# MIPI_DSI_CSI.net
KiCad netlist of a schematic drawn in Altium Designer
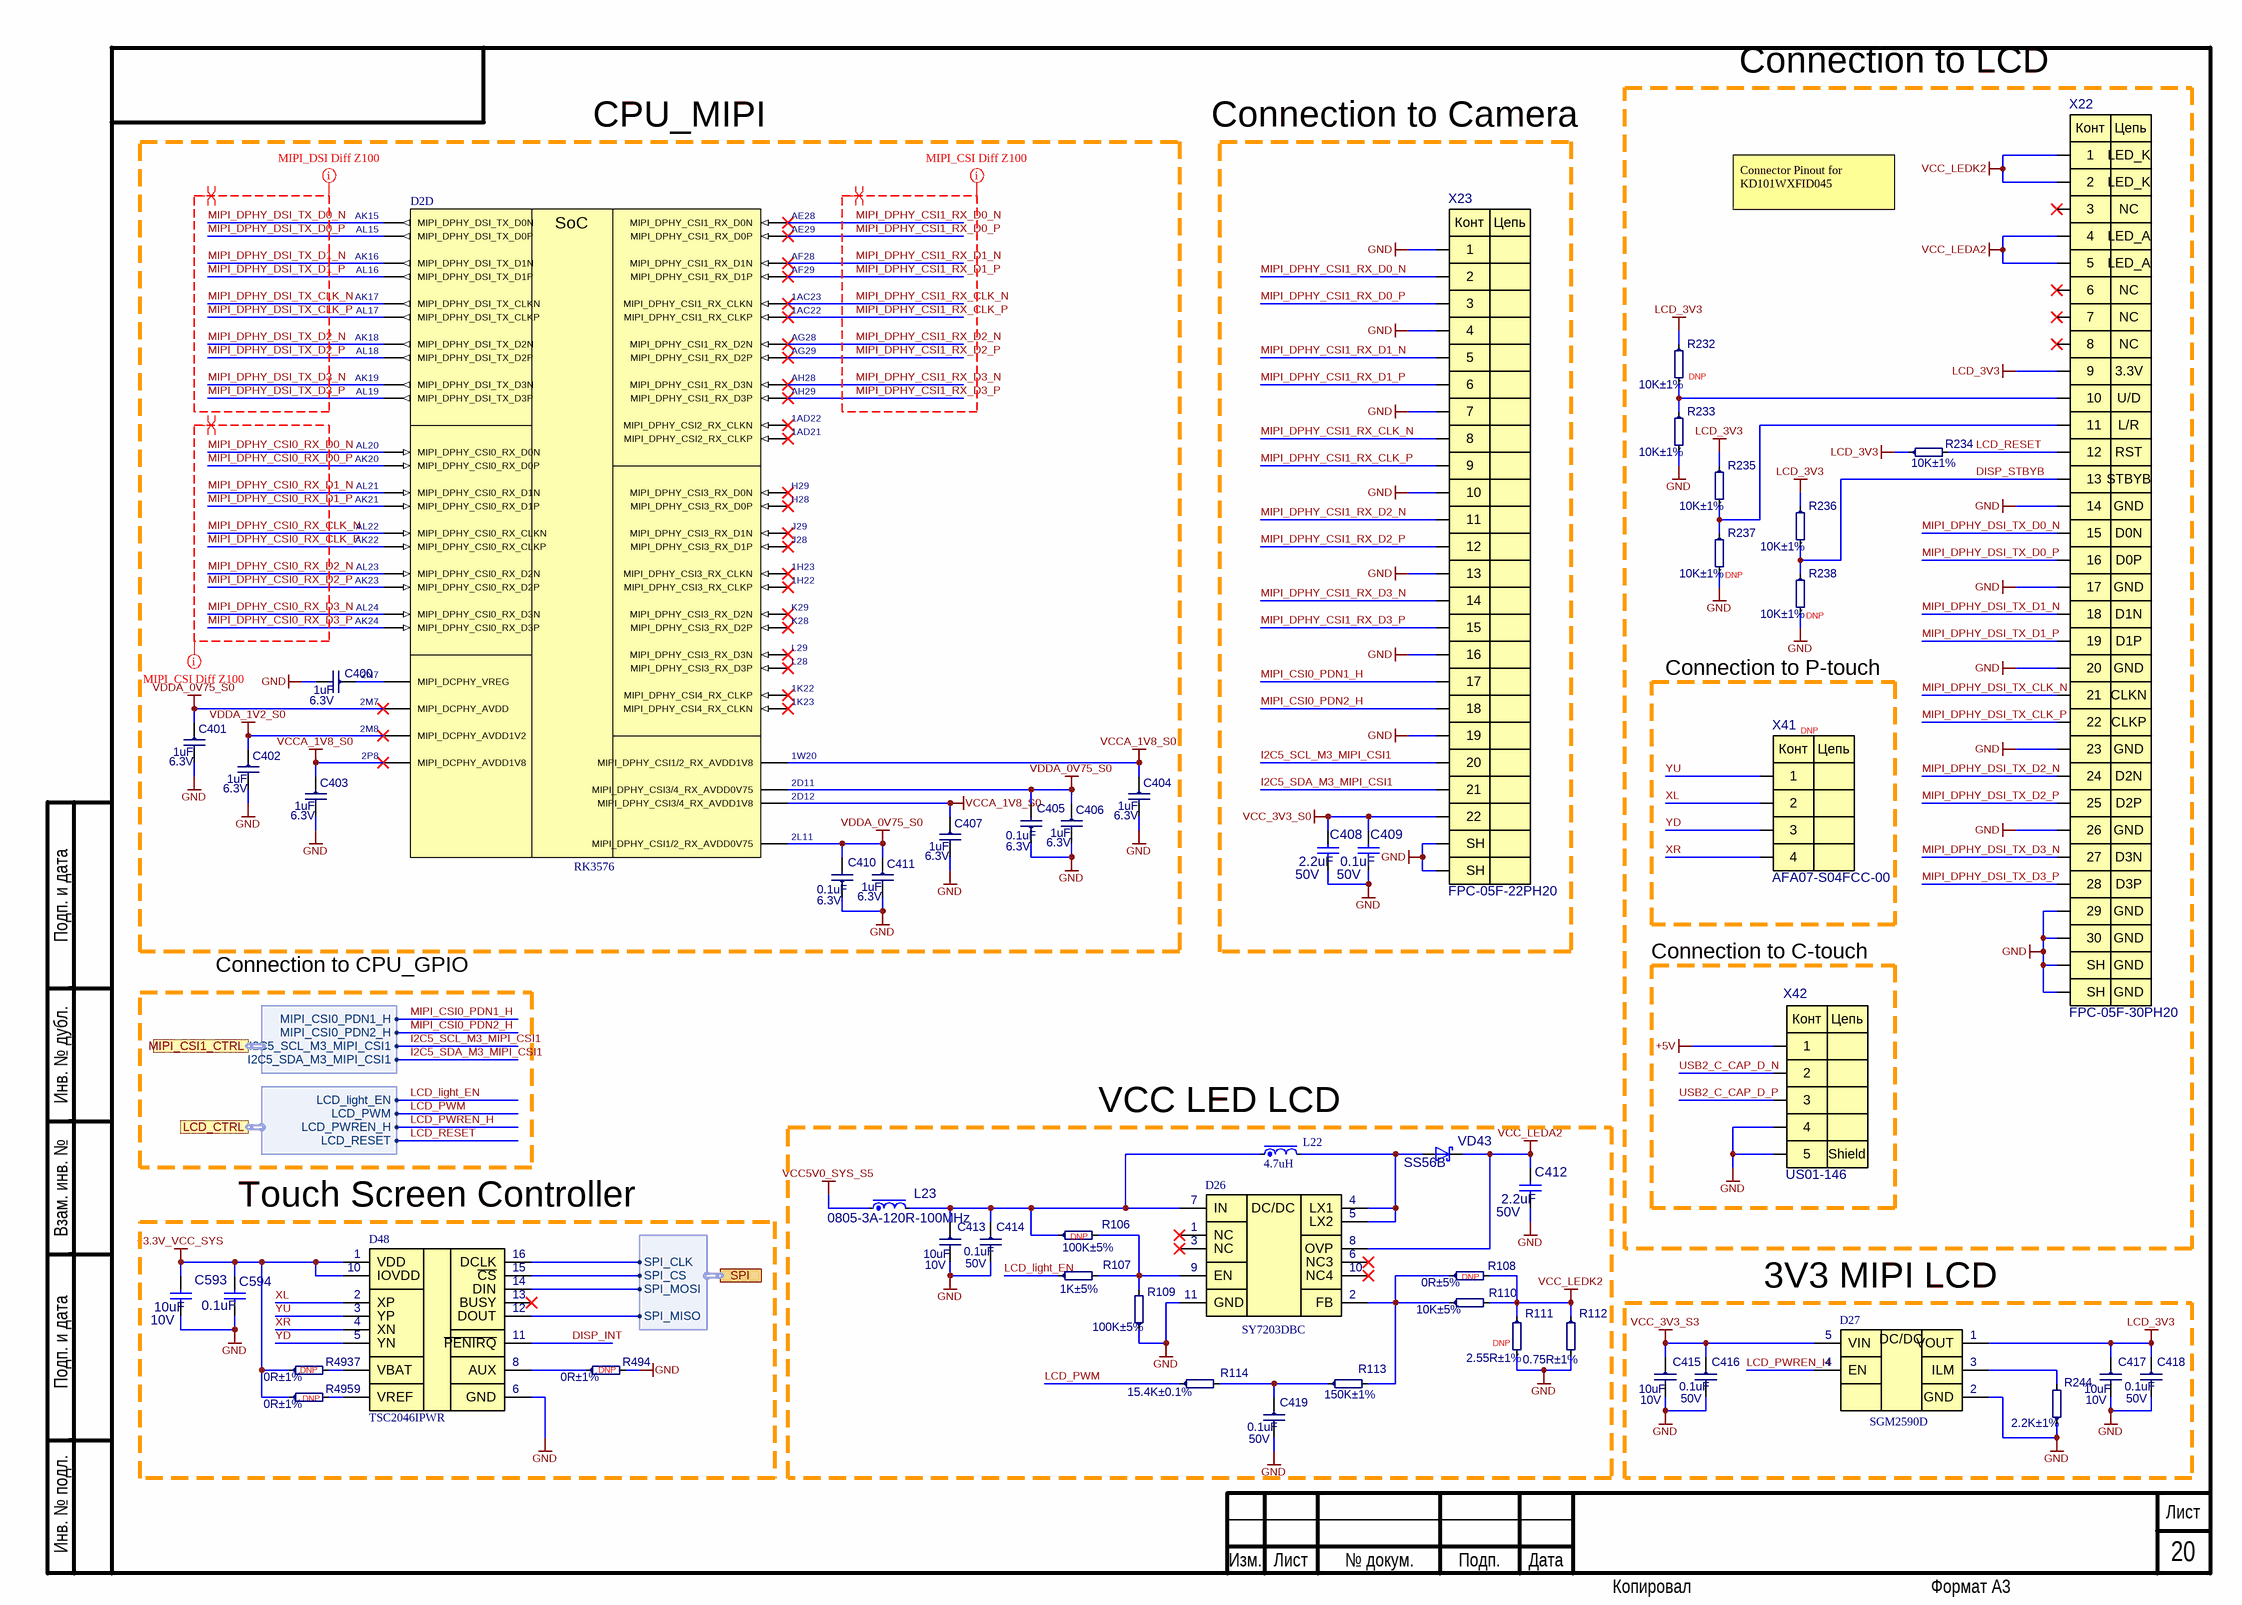
[diagram p0: MIPI_DSI_CSI.SchDoc]

(export (version "E")
  (design (tool "Eeschema 10.0.6"))
  (components
    (comp (ref "C400")
      (value "1uF")
      (footprint "C0201")
      (fields
        (field (name "VOLTAGE") "6.3V")
        (field (name "PART NUMBER") "0201-X5R-6.3V-1uF±20%")
        (field (name "TOLERANCE") "20%")
        (field (name "MANUFACTURER") "Murata Electronics")
      )
      (libsource (lib "ATB") (part "C"))
    )
    (comp (ref "C401")
      (value "1uF")
      (footprint "C0201")
      (fields
        (field (name "VOLTAGE") "6.3V")
        (field (name "PART NUMBER") "0201-X5R-6.3V-1uF±20%")
        (field (name "TOLERANCE") "20%")
        (field (name "MANUFACTURER") "Murata Electronics")
      )
      (libsource (lib "ATB") (part "C"))
    )
    (comp (ref "C402")
      (value "1uF")
      (footprint "C0201")
      (fields
        (field (name "VOLTAGE") "6.3V")
        (field (name "PART NUMBER") "0201-X5R-6.3V-1uF±20%")
        (field (name "TOLERANCE") "20%")
        (field (name "MANUFACTURER") "Murata Electronics")
      )
      (libsource (lib "ATB") (part "C"))
    )
    (comp (ref "C403")
      (value "1uF")
      (footprint "C0201")
      (fields
        (field (name "VOLTAGE") "6.3V")
        (field (name "PART NUMBER") "0201-X5R-6.3V-1uF±20%")
        (field (name "TOLERANCE") "20%")
        (field (name "MANUFACTURER") "Murata Electronics")
      )
      (libsource (lib "ATB") (part "C"))
    )
    (comp (ref "C404")
      (value "1uF")
      (footprint "C0201")
      (fields
        (field (name "VOLTAGE") "6.3V")
        (field (name "PART NUMBER") "0201-X5R-6.3V-1uF±20%")
        (field (name "TOLERANCE") "20%")
        (field (name "MANUFACTURER") "Murata Electronics")
      )
      (libsource (lib "ATB") (part "C"))
    )
    (comp (ref "C405")
      (value "0.1uF")
      (footprint "C0201")
      (fields
        (field (name "VOLTAGE") "6.3V")
        (field (name "PART NUMBER") "0201-X5R-6.3V-0.1uF±10%")
        (field (name "TOLERANCE") "10%")
        (field (name "MANUFACTURER") "Yageo")
      )
      (libsource (lib "ATB") (part "C"))
    )
    (comp (ref "C406")
      (value "1uF")
      (footprint "C0201")
      (fields
        (field (name "VOLTAGE") "6.3V")
        (field (name "PART NUMBER") "0201-X5R-6.3V-1uF±20%")
        (field (name "TOLERANCE") "20%")
        (field (name "MANUFACTURER") "Murata Electronics")
      )
      (libsource (lib "ATB") (part "C"))
    )
    (comp (ref "C407")
      (value "1uF")
      (footprint "C0201")
      (fields
        (field (name "VOLTAGE") "6.3V")
        (field (name "PART NUMBER") "0201-X5R-6.3V-1uF±20%")
        (field (name "TOLERANCE") "20%")
        (field (name "MANUFACTURER") "Murata Electronics")
      )
      (libsource (lib "ATB") (part "C"))
    )
    (comp (ref "C408")
      (value "2.2uF")
      (footprint "C0805")
      (fields
        (field (name "PART NUMBER") "0805-X7R-50V-2.2uF±10%")
        (field (name "VOLTAGE") "50V")
        (field (name "TOLERANCE") "10%")
        (field (name "MANUFACTURER") "Yageo")
      )
      (libsource (lib "") (part "C_1"))
    )
    (comp (ref "C409")
      (value "0.1uF")
      (footprint "C0402")
      (fields
        (field (name "PART NUMBER") "0402-X5R-50V-0.1uF±10%")
        (field (name "VOLTAGE") "50V")
        (field (name "TOLERANCE") "10%")
        (field (name "MANUFACTURER") "Yageo")
      )
      (libsource (lib "") (part "C_1"))
    )
    (comp (ref "C410")
      (value "0.1uF")
      (footprint "C0201")
      (fields
        (field (name "VOLTAGE") "6.3V")
        (field (name "PART NUMBER") "0201-X5R-6.3V-0.1uF±10%")
        (field (name "TOLERANCE") "10%")
        (field (name "MANUFACTURER") "Yageo")
      )
      (libsource (lib "ATB") (part "C"))
    )
    (comp (ref "C411")
      (value "1uF")
      (footprint "C0201")
      (fields
        (field (name "VOLTAGE") "6.3V")
        (field (name "PART NUMBER") "0201-X5R-6.3V-1uF±20%")
        (field (name "TOLERANCE") "20%")
        (field (name "MANUFACTURER") "Murata Electronics")
      )
      (libsource (lib "ATB") (part "C"))
    )
    (comp (ref "C412")
      (value "2.2uF")
      (footprint "C0805")
      (fields
        (field (name "PART NUMBER") "0805-X7R-50V-2.2uF±10%")
        (field (name "VOLTAGE") "50V")
        (field (name "TOLERANCE") "10%")
        (field (name "MANUFACTURER") "Yageo")
      )
      (libsource (lib "") (part "C_1"))
    )
    (comp (ref "C413")
      (value "10uF")
      (footprint "C0603")
      (fields
        (field (name "VOLTAGE") "10V")
        (field (name "PART NUMBER") "0603-X5R-10V-10uF±10%")
        (field (name "TOLERANCE") "10%")
        (field (name "MANUFACTURER") "Yageo")
      )
      (libsource (lib "ATB") (part "C"))
    )
    (comp (ref "C414")
      (value "0.1uF")
      (footprint "C0402")
      (fields
        (field (name "VOLTAGE") "50V")
        (field (name "PART NUMBER") "0402-X5R-50V-0.1uF±10%")
        (field (name "TOLERANCE") "10%")
        (field (name "MANUFACTURER") "Yageo")
      )
      (libsource (lib "ATB") (part "C"))
    )
    (comp (ref "C415")
      (value "10uF")
      (footprint "C0603")
      (fields
        (field (name "VOLTAGE") "10V")
        (field (name "PART NUMBER") "0603-X5R-10V-10uF±10%")
        (field (name "TOLERANCE") "10%")
        (field (name "MANUFACTURER") "Yageo")
      )
      (libsource (lib "ATB") (part "C"))
    )
    (comp (ref "C416")
      (value "0.1uF")
      (footprint "C0402")
      (fields
        (field (name "VOLTAGE") "50V")
        (field (name "PART NUMBER") "0402-X5R-50V-0.1uF±10%")
        (field (name "TOLERANCE") "10%")
        (field (name "MANUFACTURER") "Yageo")
      )
      (libsource (lib "ATB") (part "C"))
    )
    (comp (ref "C417")
      (value "10uF")
      (footprint "C0603")
      (fields
        (field (name "VOLTAGE") "10V")
        (field (name "PART NUMBER") "0603-X5R-10V-10uF±10%")
        (field (name "TOLERANCE") "10%")
        (field (name "MANUFACTURER") "Yageo")
      )
      (libsource (lib "ATB") (part "C"))
    )
    (comp (ref "C418")
      (value "0.1uF")
      (footprint "C0402")
      (fields
        (field (name "VOLTAGE") "50V")
        (field (name "PART NUMBER") "0402-X5R-50V-0.1uF±10%")
        (field (name "TOLERANCE") "10%")
        (field (name "MANUFACTURER") "Yageo")
      )
      (libsource (lib "ATB") (part "C"))
    )
    (comp (ref "C419")
      (value "0.1uF")
      (footprint "C0402")
      (fields
        (field (name "VOLTAGE") "50V")
        (field (name "PART NUMBER") "0402-X5R-50V-0.1uF±10%")
        (field (name "TOLERANCE") "10%")
        (field (name "MANUFACTURER") "Yageo")
      )
      (libsource (lib "ATB") (part "C"))
    )
    (comp (ref "C593")
      (value "10uF")
      (footprint "C0402")
      (fields
        (field (name "PART NUMBER") "0402-X5R-10V-10uF±20")
        (field (name "VOLTAGE") "10V")
        (field (name "TOLERANCE") "20%")
        (field (name "MANUFACTURER") "Samsung")
      )
      (libsource (lib "") (part "C_1"))
    )
    (comp (ref "C594")
      (value "0.1uF")
      (footprint "C0402")
      (fields
        (field (name "PART NUMBER") "0402-X5R-50V-0.1uF±10%")
        (field (name "VOLTAGE") "50V")
        (field (name "TOLERANCE") "10%")
      )
      (libsource (lib "") (part "C_1"))
    )
    (comp (ref "D2")
      (value "RK3576")
      (footprint "BGAFCCSP698L")
      (description "SoC 4xCortex-A72@2.2Ghz+4xCortex-A53@2Ghz, LPDDR4/4X/5/5X, SDIO/eMMC/UFS/FSPI, BGA 16.1x17.2x1.0mm")
      (fields (field (name "MANUFACTURER") "Rockship"))
      (libsource (lib "ATB") (part "RK3576"))
    )
    (comp (ref "D26")
      (value "SY7203DBC")
      (footprint "SY7203DBC")
      (description "1MHz PWM Boost 1 DC-DC 2.8V~30V DFN-10-EP(3x3) LED Drivers ICs RoHS")
      (fields (field (name "MANUFACTURER") "Silergy"))
      (libsource (lib "LIB_RK") (part "SY7203DBC"))
    )
    (comp (ref "D27")
      (value "SGM2590D")
      (footprint "SGM2590D")
      (fields (field (name "MANUFACTURER") "SGM"))
      (libsource (lib "LIB_RK") (part "SGM2590D"))
    )
    (comp (ref "D48")
      (value "TSC2046IPWR")
      (footprint "TSC2046IPWR")
      (description "SPI 12 2.2V~5.25V TSSOP-16 Touch Screen Controllers")
      (fields (field (name "MANUFACTURER") "Texas"))
      (libsource (lib "LIB_RK") (part "TSC2046IPWR"))
    )
    (comp (ref "L22")
      (value "4.7uH")
      (footprint "SWPA6045S4R7MT")
      (description "SMD Power Inductor")
      (fields (field (name "PART NUMBER") "SWPA6045S4R7MT") (field (name "MANUFACTURER") "Sunlord"))
      (libsource (lib "LIB_RK") (part "SWPA6045S4R7MT"))
    )
    (comp (ref "L23")
      (value "0805-3A-120R-100MHz")
      (footprint "L0805")
      (fields
        (field (name "PART NUMBER") "CBM201209U121T")
        (field (name "TOLERANCE") "25%")
        (field (name "MANUFACTURER") "FH")
      )
      (libsource (lib "ATB") (part "L"))
    )
    (comp (ref "R106")
      (value "100K±5%")
      (footprint "R0402")
      (fields
        (field (name "PART NUMBER") "0402-0.0625W-100K-100ppm±5%")
        (field (name "TOLERANCE") "5%")
        (field (name "MANUFACTURER") "Yageo")
      )
      (libsource (lib "ATB") (part "R"))
    )
    (comp (ref "R107")
      (value "1K±5%")
      (footprint "R0402")
      (fields
        (field (name "PART NUMBER") "0402-0.0625W-1K-100ppm±5%")
        (field (name "TOLERANCE") "5%")
        (field (name "MANUFACTURER") "Yageo")
      )
      (libsource (lib "ATB") (part "R"))
    )
    (comp (ref "R108")
      (value "0R±5%")
      (footprint "R1206")
      (fields
        (field (name "PART NUMBER") "1206-0.25W-0R-200ppm±5%")
        (field (name "TOLERANCE") "5%")
        (field (name "MANUFACTURER") "Yageo")
      )
      (libsource (lib "ATB") (part "R"))
    )
    (comp (ref "R109")
      (value "100K±5%")
      (footprint "R0402")
      (fields
        (field (name "PART NUMBER") "0402-0.0625W-100K-100ppm±5%")
        (field (name "TOLERANCE") "5%")
        (field (name "MANUFACTURER") "Yageo")
      )
      (libsource (lib "ATB") (part "R"))
    )
    (comp (ref "R110")
      (value "10K±5%")
      (footprint "R1206")
      (fields
        (field (name "PART NUMBER") "1206-0.25W-10K-100ppm±5%")
        (field (name "TOLERANCE") "5%")
        (field (name "MANUFACTURER") "Yageo")
      )
      (libsource (lib "ATB") (part "R"))
    )
    (comp (ref "R111")
      (value "2.55R±1%")
      (footprint "R1206")
      (fields
        (field (name "PART NUMBER") "1206-0.25W-2.55R-100ppm±1%")
        (field (name "TOLERANCE") "1%")
        (field (name "MANUFACTURER") "Yageo")
      )
      (libsource (lib "ATB") (part "R"))
    )
    (comp (ref "R112")
      (value "0.75R±1%")
      (footprint "R1206")
      (fields
        (field (name "PART NUMBER") "1206-0.25W-0.75R-100ppm±1%")
        (field (name "TOLERANCE") "1%")
        (field (name "MANUFACTURER") "UNI-ROYAL")
      )
      (libsource (lib "ATB") (part "R"))
    )
    (comp (ref "R113")
      (value "150K±1%")
      (footprint "R0402")
      (fields
        (field (name "PART NUMBER") "0402-0.0625W-150K-100ppm±1%")
        (field (name "TOLERANCE") "1%")
        (field (name "MANUFACTURER") "Yageo")
      )
      (libsource (lib "ATB") (part "R"))
    )
    (comp (ref "R114")
      (value "15.4K±0.1%")
      (footprint "R0603")
      (fields
        (field (name "PART NUMBER") "0603-0.1W-15.4K-25ppm±0.1%")
        (field (name "TOLERANCE") "0.1%")
        (field (name "MANUFACTURER") "Yageo")
      )
      (libsource (lib "ATB") (part "R"))
    )
    (comp (ref "R232")
      (value "10K±1%")
      (footprint "R0402")
      (description "Chip Resistor 0402 10kΩ ±1% 50V ±100ppm/℃ Thick Film")
      (fields (field (name "PART NUMBER") "0402-0.0625W-10K-100ppm±1%") (field (name "TOLERANCE") "1%"))
      (libsource (lib "ATB") (part "R"))
    )
    (comp (ref "R233")
      (value "10K±1%")
      (footprint "R0402")
      (description "Chip Resistor 0402 10kΩ ±1% 50V ±100ppm/℃ Thick Film")
      (fields (field (name "PART NUMBER") "0402-0.0625W-10K-100ppm±1%") (field (name "TOLERANCE") "1%"))
      (libsource (lib "ATB") (part "R"))
    )
    (comp (ref "R234")
      (value "10K±1%")
      (footprint "R0402")
      (description "Chip Resistor 0402 10kΩ ±1% 50V ±100ppm/℃ Thick Film")
      (fields (field (name "PART NUMBER") "0402-0.0625W-10K-100ppm±1%") (field (name "TOLERANCE") "1%"))
      (libsource (lib "ATB") (part "R"))
    )
    (comp (ref "R235")
      (value "10K±1%")
      (footprint "R0402")
      (description "Chip Resistor 0402 10kΩ ±1% 50V ±100ppm/℃ Thick Film")
      (fields (field (name "PART NUMBER") "0402-0.0625W-10K-100ppm±1%") (field (name "TOLERANCE") "1%"))
      (libsource (lib "ATB") (part "R"))
    )
    (comp (ref "R236")
      (value "10K±1%")
      (footprint "R0402")
      (description "Chip Resistor 0402 10kΩ ±1% 50V ±100ppm/℃ Thick Film")
      (fields (field (name "PART NUMBER") "0402-0.0625W-10K-100ppm±1%") (field (name "TOLERANCE") "1%"))
      (libsource (lib "ATB") (part "R"))
    )
    (comp (ref "R237")
      (value "10K±1%")
      (footprint "R0402")
      (description "Chip Resistor 0402 10kΩ ±1% 50V ±100ppm/℃ Thick Film")
      (fields (field (name "PART NUMBER") "0402-0.0625W-10K-100ppm±1%") (field (name "TOLERANCE") "1%"))
      (libsource (lib "ATB") (part "R"))
    )
    (comp (ref "R238")
      (value "10K±1%")
      (footprint "R0402")
      (description "Chip Resistor 0402 10kΩ ±1% 50V ±100ppm/℃ Thick Film")
      (fields (field (name "PART NUMBER") "0402-0.0625W-10K-100ppm±1%") (field (name "TOLERANCE") "1%"))
      (libsource (lib "ATB") (part "R"))
    )
    (comp (ref "R244")
      (value "2.2K±1%")
      (footprint "R0402")
      (fields
        (field (name "PART NUMBER") "0402-0.0625W-2.2K-100ppm±1%")
        (field (name "TOLERANCE") "1%")
        (field (name "MANUFACTURER") "Yageo")
      )
      (libsource (lib "ATB") (part "R"))
    )
    (comp (ref "R493")
      (value "0R±1%")
      (footprint "R0402")
      (description "Chip Resistor 0402 0Ω ±1% 50V ±100ppm/℃ Thick Film")
      (fields (field (name "PART NUMBER") "0402-0.0625W-0R-100ppm±1%") (field (name "TOLERANCE") "1%"))
      (libsource (lib "ATB") (part "R"))
    )
    (comp (ref "R494")
      (value "0R±1%")
      (footprint "R0402")
      (description "Chip Resistor 0402 0Ω ±1% 50V ±100ppm/℃ Thick Film")
      (fields (field (name "PART NUMBER") "0402-0.0625W-0R-100ppm±1%") (field (name "TOLERANCE") "1%"))
      (libsource (lib "ATB") (part "R"))
    )
    (comp (ref "R495")
      (value "0R±1%")
      (footprint "R0402")
      (description "Chip Resistor 0402 0Ω ±1% 50V ±100ppm/℃ Thick Film")
      (fields (field (name "PART NUMBER") "0402-0.0625W-0R-100ppm±1%") (field (name "TOLERANCE") "1%"))
      (libsource (lib "ATB") (part "R"))
    )
    (comp (ref "VD43")
      (value "SS56B")
      (footprint "DO-214AA")
      (description "Schottky Rectifier")
      (fields (field (name "MANUFACTURER") "Yangjie (YJ)"))
      (libsource (lib "ATB") (part "Shotki"))
    )
    (comp (ref "X22")
      (value "FPC-05F-30PH20")
      (footprint "FPC-05F-30PH20")
      (fields (field (name "MANUFACTURER") "XUNPU"))
      (libsource (lib "LIB_RK") (part "FPC-05F-30PH20"))
    )
    (comp (ref "X23")
      (value "FPC-05F-22PH20")
      (footprint "FPC-05F-22PH20")
      (description "FFC/FPC Connector 22 Position 0.5mm Pitch Bottom Contact Surface Mount, Right Angle -25℃~+85℃")
      (fields (field (name "MANUFACTURER") "XUNPU"))
      (libsource (lib "LIB_RK") (part "FPC-05F-22PH20"))
    )
    (comp (ref "X41")
      (value "AFA07-S04FCC-00")
      (footprint "AFA07-S04FCC-00")
      (fields (field (name "MANUFACTURER") "JUSHUO"))
      (libsource (lib "LIB_RK") (part "AFA07-S04FCC-00"))
    )
    (comp (ref "X42")
      (value "US01-146")
      (footprint "US01-146")
      (description "USB Female SMT 90° A type")
      (fields (field (name "MANUFACTURER") "Dart"))
      (libsource (lib "ATB") (part "DS1095-WNR0"))
    )
  )
  (nets
    (net (code "4") (name "+3.3V_VCC_SYS") (class "Default")
      (node (ref "C593") (pin "2") (pinfunction "2_2") (pintype "passive"))
      (node (ref "C594") (pin "2") (pinfunction "2_2") (pintype "passive"))
      (node (ref "D48") (pin "1") (pinfunction "VDD_1") (pintype "passive"))
      (node (ref "D48") (pin "10") (pinfunction "IOVDD_10") (pintype "passive"))
      (node (ref "R493") (pin "1") (pinfunction "1_1") (pintype "passive"))
      (node (ref "R495") (pin "1") (pinfunction "1_1") (pintype "passive"))
    )
    (net (code "5") (name "+5V") (class "Default")
      (node (ref "X42") (pin "1") (pinfunction "1_1") (pintype "passive"))
    )
    (net (code "6") (name "/DISP_INT") (class "Default")
      (node (ref "D48") (pin "11") (pinfunction "~{PENIRQ}_11") (pintype "passive"))
    )
    (net (code "7") (name "/DISP_STBYB") (class "Default")
      (node (ref "R236") (pin "2") (pinfunction "2_2") (pintype "passive"))
      (node (ref "R238") (pin "1") (pinfunction "1_1") (pintype "passive"))
      (node (ref "X22") (pin "13") (pinfunction "13_13") (pintype "passive"))
    )
    (net (code "8") (name "/I2C5_SCL_M3_MIPI_CSI1") (class "Default")
      (node (ref "X23") (pin "20") (pinfunction "20_20") (pintype "passive"))
    )
    (net (code "9") (name "/I2C5_SDA_M3_MIPI_CSI1") (class "Default")
      (node (ref "X23") (pin "21") (pinfunction "21_21") (pintype "passive"))
    )
    (net (code "10") (name "/LCD_PWM") (class "Default")
      (node (ref "R114") (pin "1") (pinfunction "1_1") (pintype "passive"))
    )
    (net (code "11") (name "/LCD_PWREN_H") (class "Default")
      (node (ref "D27") (pin "4") (pinfunction "EN_4") (pintype "passive"))
    )
    (net (code "12") (name "/LCD_RESET") (class "Default")
      (node (ref "R234") (pin "2") (pinfunction "2_2") (pintype "passive"))
      (node (ref "X22") (pin "12") (pinfunction "12_12") (pintype "passive"))
    )
    (net (code "13") (name "/LCD_light_EN") (class "Default")
      (node (ref "R107") (pin "1") (pinfunction "1_1") (pintype "passive"))
    )
    (net (code "14") (name "/MIPI_CSI0_PDN1_H") (class "Default")
      (node (ref "X23") (pin "17") (pinfunction "17_17") (pintype "passive"))
    )
    (net (code "15") (name "/MIPI_CSI0_PDN2_H") (class "Default")
      (node (ref "X23") (pin "18") (pinfunction "18_18") (pintype "passive"))
    )
    (net (code "16") (name "/MIPI_DPHY_CSI0_RX_CLK_N") (class "Default")
      (node (ref "D2") (pin "AL22") (pinfunction "MIPI_DPHY_CSI0_RX_CLKN_AL22") (pintype "input"))
    )
    (net (code "17") (name "/MIPI_DPHY_CSI0_RX_CLK_P") (class "Default")
      (node (ref "D2") (pin "AK22") (pinfunction "MIPI_DPHY_CSI0_RX_CLKP_AK22") (pintype "input"))
    )
    (net (code "18") (name "/MIPI_DPHY_CSI0_RX_D0_N") (class "Default")
      (node (ref "D2") (pin "AL20") (pinfunction "MIPI_DPHY_CSI0_RX_D0N_AL20") (pintype "input"))
    )
    (net (code "19") (name "/MIPI_DPHY_CSI0_RX_D0_P") (class "Default")
      (node (ref "D2") (pin "AK20") (pinfunction "MIPI_DPHY_CSI0_RX_D0P_AK20") (pintype "input"))
    )
    (net (code "20") (name "/MIPI_DPHY_CSI0_RX_D1_N") (class "Default")
      (node (ref "D2") (pin "AL21") (pinfunction "MIPI_DPHY_CSI0_RX_D1N_AL21") (pintype "input"))
    )
    (net (code "21") (name "/MIPI_DPHY_CSI0_RX_D1_P") (class "Default")
      (node (ref "D2") (pin "AK21") (pinfunction "MIPI_DPHY_CSI0_RX_D1P_AK21") (pintype "input"))
    )
    (net (code "22") (name "/MIPI_DPHY_CSI0_RX_D2_N") (class "Default")
      (node (ref "D2") (pin "AL23") (pinfunction "MIPI_DPHY_CSI0_RX_D2N_AL23") (pintype "input"))
    )
    (net (code "23") (name "/MIPI_DPHY_CSI0_RX_D2_P") (class "Default")
      (node (ref "D2") (pin "AK23") (pinfunction "MIPI_DPHY_CSI0_RX_D2P_AK23") (pintype "input"))
    )
    (net (code "24") (name "/MIPI_DPHY_CSI0_RX_D3_N") (class "Default")
      (node (ref "D2") (pin "AL24") (pinfunction "MIPI_DPHY_CSI0_RX_D3N_AL24") (pintype "input"))
    )
    (net (code "25") (name "/MIPI_DPHY_CSI0_RX_D3_P") (class "Default")
      (node (ref "D2") (pin "AK24") (pinfunction "MIPI_DPHY_CSI0_RX_D3P_AK24") (pintype "input"))
    )
    (net (code "26") (name "/MIPI_DPHY_CSI1_RX_CLK_N") (class "Default")
      (node (ref "D2") (pin "1AC23") (pinfunction "MIPI_DPHY_CSI1_RX_CLKN_1AC23") (pintype "input"))
      (node (ref "X23") (pin "8") (pinfunction "8_8") (pintype "passive"))
    )
    (net (code "27") (name "/MIPI_DPHY_CSI1_RX_CLK_P") (class "Default")
      (node (ref "D2") (pin "1AC22") (pinfunction "MIPI_DPHY_CSI1_RX_CLKP_1AC22") (pintype "input"))
      (node (ref "X23") (pin "9") (pinfunction "9_9") (pintype "passive"))
    )
    (net (code "28") (name "/MIPI_DPHY_CSI1_RX_D0_N") (class "Default")
      (node (ref "D2") (pin "AE28") (pinfunction "MIPI_DPHY_CSI1_RX_D0N_AE28") (pintype "input"))
      (node (ref "X23") (pin "2") (pinfunction "2_2") (pintype "passive"))
    )
    (net (code "29") (name "/MIPI_DPHY_CSI1_RX_D0_P") (class "Default")
      (node (ref "D2") (pin "AE29") (pinfunction "MIPI_DPHY_CSI1_RX_D0P_AE29") (pintype "input"))
      (node (ref "X23") (pin "3") (pinfunction "3_3") (pintype "passive"))
    )
    (net (code "30") (name "/MIPI_DPHY_CSI1_RX_D1_N") (class "Default")
      (node (ref "D2") (pin "AF28") (pinfunction "MIPI_DPHY_CSI1_RX_D1N_AF28") (pintype "input"))
      (node (ref "X23") (pin "5") (pinfunction "5_5") (pintype "passive"))
    )
    (net (code "31") (name "/MIPI_DPHY_CSI1_RX_D1_P") (class "Default")
      (node (ref "D2") (pin "AF29") (pinfunction "MIPI_DPHY_CSI1_RX_D1P_AF29") (pintype "input"))
      (node (ref "X23") (pin "6") (pinfunction "6_6") (pintype "passive"))
    )
    (net (code "32") (name "/MIPI_DPHY_CSI1_RX_D2_N") (class "Default")
      (node (ref "D2") (pin "AG28") (pinfunction "MIPI_DPHY_CSI1_RX_D2N_AG28") (pintype "input"))
      (node (ref "X23") (pin "11") (pinfunction "11_11") (pintype "passive"))
    )
    (net (code "33") (name "/MIPI_DPHY_CSI1_RX_D2_P") (class "Default")
      (node (ref "D2") (pin "AG29") (pinfunction "MIPI_DPHY_CSI1_RX_D2P_AG29") (pintype "input"))
      (node (ref "X23") (pin "12") (pinfunction "12_12") (pintype "passive"))
    )
    (net (code "34") (name "/MIPI_DPHY_CSI1_RX_D3_N") (class "Default")
      (node (ref "D2") (pin "AH28") (pinfunction "MIPI_DPHY_CSI1_RX_D3N_AH28") (pintype "input"))
      (node (ref "X23") (pin "14") (pinfunction "14_14") (pintype "passive"))
    )
    (net (code "35") (name "/MIPI_DPHY_CSI1_RX_D3_P") (class "Default")
      (node (ref "D2") (pin "AH29") (pinfunction "MIPI_DPHY_CSI1_RX_D3P_AH29") (pintype "input"))
      (node (ref "X23") (pin "15") (pinfunction "15_15") (pintype "passive"))
    )
    (net (code "36") (name "/MIPI_DPHY_DSI_TX_CLK_N") (class "Default")
      (node (ref "D2") (pin "AK17") (pinfunction "MIPI_DPHY_DSI_TX_CLKN_AK17") (pintype "output"))
      (node (ref "X22") (pin "21") (pinfunction "21_21") (pintype "passive"))
    )
    (net (code "37") (name "/MIPI_DPHY_DSI_TX_CLK_P") (class "Default")
      (node (ref "D2") (pin "AL17") (pinfunction "MIPI_DPHY_DSI_TX_CLKP_AL17") (pintype "output"))
      (node (ref "X22") (pin "22") (pinfunction "22_22") (pintype "passive"))
    )
    (net (code "38") (name "/MIPI_DPHY_DSI_TX_D0_N") (class "Default")
      (node (ref "D2") (pin "AK15") (pinfunction "MIPI_DPHY_DSI_TX_D0N_AK15") (pintype "output"))
      (node (ref "X22") (pin "15") (pinfunction "15_15") (pintype "passive"))
    )
    (net (code "39") (name "/MIPI_DPHY_DSI_TX_D0_P") (class "Default")
      (node (ref "D2") (pin "AL15") (pinfunction "MIPI_DPHY_DSI_TX_D0P_AL15") (pintype "output"))
      (node (ref "X22") (pin "16") (pinfunction "16_16") (pintype "passive"))
    )
    (net (code "40") (name "/MIPI_DPHY_DSI_TX_D1_N") (class "Default")
      (node (ref "D2") (pin "AK16") (pinfunction "MIPI_DPHY_DSI_TX_D1N_AK16") (pintype "output"))
      (node (ref "X22") (pin "18") (pinfunction "18_18") (pintype "passive"))
    )
    (net (code "41") (name "/MIPI_DPHY_DSI_TX_D1_P") (class "Default")
      (node (ref "D2") (pin "AL16") (pinfunction "MIPI_DPHY_DSI_TX_D1P_AL16") (pintype "output"))
      (node (ref "X22") (pin "19") (pinfunction "19_19") (pintype "passive"))
    )
    (net (code "42") (name "/MIPI_DPHY_DSI_TX_D2_N") (class "Default")
      (node (ref "D2") (pin "AK18") (pinfunction "MIPI_DPHY_DSI_TX_D2N_AK18") (pintype "output"))
      (node (ref "X22") (pin "24") (pinfunction "24_24") (pintype "passive"))
    )
    (net (code "43") (name "/MIPI_DPHY_DSI_TX_D2_P") (class "Default")
      (node (ref "D2") (pin "AL18") (pinfunction "MIPI_DPHY_DSI_TX_D2P_AL18") (pintype "output"))
      (node (ref "X22") (pin "25") (pinfunction "25_25") (pintype "passive"))
    )
    (net (code "44") (name "/MIPI_DPHY_DSI_TX_D3_N") (class "Default")
      (node (ref "D2") (pin "AK19") (pinfunction "MIPI_DPHY_DSI_TX_D3N_AK19") (pintype "output"))
      (node (ref "X22") (pin "27") (pinfunction "27_27") (pintype "passive"))
    )
    (net (code "45") (name "/MIPI_DPHY_DSI_TX_D3_P") (class "Default")
      (node (ref "D2") (pin "AL19") (pinfunction "MIPI_DPHY_DSI_TX_D3P_AL19") (pintype "output"))
      (node (ref "X22") (pin "28") (pinfunction "28_28") (pintype "passive"))
    )
    (net (code "46") (name "/SPI_CLK") (class "Default")
      (node (ref "D48") (pin "16") (pinfunction "DCLK_16") (pintype "passive"))
    )
    (net (code "47") (name "/SPI_CS") (class "Default")
      (node (ref "D48") (pin "15") (pinfunction "~{CS}_15") (pintype "passive"))
    )
    (net (code "48") (name "/SPI_MISO") (class "Default")
      (node (ref "D48") (pin "12") (pinfunction "DOUT_12") (pintype "passive"))
    )
    (net (code "49") (name "/SPI_MOSI") (class "Default")
      (node (ref "D48") (pin "14") (pinfunction "DIN_14") (pintype "passive"))
    )
    (net (code "50") (name "/USB2_C_CAP_D_N") (class "Default")
      (node (ref "X42") (pin "2") (pinfunction "2_2") (pintype "passive"))
    )
    (net (code "51") (name "/USB2_C_CAP_D_P") (class "Default")
      (node (ref "X42") (pin "3") (pinfunction "3_3") (pintype "passive"))
    )
    (net (code "52") (name "/XL") (class "Default")
      (node (ref "D48") (pin "2") (pinfunction "XP_2") (pintype "passive"))
      (node (ref "X41") (pin "2") (pinfunction "2_2") (pintype "passive"))
    )
    (net (code "53") (name "/XR") (class "Default")
      (node (ref "D48") (pin "4") (pinfunction "XN_4") (pintype "passive"))
      (node (ref "X41") (pin "4") (pinfunction "4_4") (pintype "passive"))
    )
    (net (code "54") (name "/YD") (class "Default")
      (node (ref "D48") (pin "5") (pinfunction "YN_5") (pintype "passive"))
      (node (ref "X41") (pin "3") (pinfunction "3_3") (pintype "passive"))
    )
    (net (code "55") (name "/YU") (class "Default")
      (node (ref "D48") (pin "3") (pinfunction "YP_3") (pintype "passive"))
      (node (ref "X41") (pin "1") (pinfunction "1_1") (pintype "passive"))
    )
    (net (code "59") (name "GND") (class "Default")
      (node (ref "C400") (pin "2") (pinfunction "2_2") (pintype "passive"))
      (node (ref "C401") (pin "2") (pinfunction "2_2") (pintype "passive"))
      (node (ref "C402") (pin "2") (pinfunction "2_2") (pintype "passive"))
      (node (ref "C403") (pin "2") (pinfunction "2_2") (pintype "passive"))
      (node (ref "C404") (pin "2") (pinfunction "2_2") (pintype "passive"))
      (node (ref "C405") (pin "1") (pinfunction "1_1") (pintype "passive"))
      (node (ref "C406") (pin "2") (pinfunction "2_2") (pintype "passive"))
      (node (ref "C407") (pin "2") (pinfunction "2_2") (pintype "passive"))
      (node (ref "C408") (pin "1") (pinfunction "1_1") (pintype "passive"))
      (node (ref "C409") (pin "1") (pinfunction "1_1") (pintype "passive"))
      (node (ref "C410") (pin "1") (pinfunction "1_1") (pintype "passive"))
      (node (ref "C411") (pin "2") (pinfunction "2_2") (pintype "passive"))
      (node (ref "C412") (pin "1") (pinfunction "1_1") (pintype "passive"))
      (node (ref "C413") (pin "2") (pinfunction "2_2") (pintype "passive"))
      (node (ref "C414") (pin "2") (pinfunction "2_2") (pintype "passive"))
      (node (ref "C415") (pin "2") (pinfunction "2_2") (pintype "passive"))
      (node (ref "C416") (pin "2") (pinfunction "2_2") (pintype "passive"))
      (node (ref "C417") (pin "2") (pinfunction "2_2") (pintype "passive"))
      (node (ref "C418") (pin "2") (pinfunction "2_2") (pintype "passive"))
      (node (ref "C419") (pin "2") (pinfunction "2_2") (pintype "passive"))
      (node (ref "C593") (pin "1") (pinfunction "1_1") (pintype "passive"))
      (node (ref "C594") (pin "1") (pinfunction "1_1") (pintype "passive"))
      (node (ref "D26") (pin "11") (pinfunction "GND_11") (pintype "passive"))
      (node (ref "D27") (pin "2") (pinfunction "GND_2") (pintype "passive"))
      (node (ref "D48") (pin "6") (pinfunction "GND_6") (pintype "passive"))
      (node (ref "R109") (pin "1") (pinfunction "1_1") (pintype "passive"))
      (node (ref "R111") (pin "2") (pinfunction "2_2") (pintype "passive"))
      (node (ref "R112") (pin "2") (pinfunction "2_2") (pintype "passive"))
      (node (ref "R233") (pin "2") (pinfunction "2_2") (pintype "passive"))
      (node (ref "R237") (pin "2") (pinfunction "2_2") (pintype "passive"))
      (node (ref "R238") (pin "2") (pinfunction "2_2") (pintype "passive"))
      (node (ref "R244") (pin "1") (pinfunction "1_1") (pintype "passive"))
      (node (ref "R494") (pin "2") (pinfunction "2_2") (pintype "passive"))
      (node (ref "X22") (pin "14") (pinfunction "14_14") (pintype "passive"))
      (node (ref "X22") (pin "17") (pinfunction "17_17") (pintype "passive"))
      (node (ref "X22") (pin "20") (pinfunction "20_20") (pintype "passive"))
      (node (ref "X22") (pin "23") (pinfunction "23_23") (pintype "passive"))
      (node (ref "X22") (pin "26") (pinfunction "26_26") (pintype "passive"))
      (node (ref "X22") (pin "29") (pinfunction "29_29") (pintype "passive"))
      (node (ref "X22") (pin "30") (pinfunction "30_30") (pintype "passive"))
      (node (ref "X22") (pin "S1") (pinfunction "SH_S1") (pintype "passive"))
      (node (ref "X22") (pin "S2") (pinfunction "SH_S2") (pintype "passive"))
      (node (ref "X23") (pin "1") (pinfunction "1_1") (pintype "passive"))
      (node (ref "X23") (pin "10") (pinfunction "10_10") (pintype "passive"))
      (node (ref "X23") (pin "13") (pinfunction "13_13") (pintype "passive"))
      (node (ref "X23") (pin "16") (pinfunction "16_16") (pintype "passive"))
      (node (ref "X23") (pin "19") (pinfunction "19_19") (pintype "passive"))
      (node (ref "X23") (pin "23") (pinfunction "SH_23") (pintype "passive"))
      (node (ref "X23") (pin "24") (pinfunction "SH_24") (pintype "passive"))
      (node (ref "X23") (pin "4") (pinfunction "4_4") (pintype "passive"))
      (node (ref "X23") (pin "7") (pinfunction "7_7") (pintype "passive"))
      (node (ref "X42") (pin "4") (pinfunction "4_4") (pintype "passive"))
      (node (ref "X42") (pin "5") (pinfunction "5_5") (pintype "passive"))
    )
    (net (code "60") (name "LCD_3V3") (class "Default")
      (node (ref "C417") (pin "1") (pinfunction "1_1") (pintype "passive"))
      (node (ref "C418") (pin "1") (pinfunction "1_1") (pintype "passive"))
      (node (ref "D27") (pin "1") (pinfunction "VOUT_1") (pintype "passive"))
      (node (ref "R232") (pin "1") (pinfunction "1_1") (pintype "passive"))
      (node (ref "R234") (pin "1") (pinfunction "1_1") (pintype "passive"))
      (node (ref "R235") (pin "1") (pinfunction "1_1") (pintype "passive"))
      (node (ref "R236") (pin "1") (pinfunction "1_1") (pintype "passive"))
      (node (ref "X22") (pin "9") (pinfunction "9_9") (pintype "passive"))
    )
    (net (code "61") (name "Net-(C419-Pad1)") (class "Default")
      (node (ref "C419") (pin "1") (pinfunction "1_1") (pintype "passive"))
      (node (ref "R113") (pin "1") (pinfunction "1_1") (pintype "passive"))
      (node (ref "R114") (pin "2") (pinfunction "2_2") (pintype "passive"))
    )
    (net (code "62") (name "Net-(D2D-MIPI_DCPHY_VREG)") (class "Default")
      (node (ref "C400") (pin "1") (pinfunction "1_1") (pintype "passive"))
      (node (ref "D2") (pin "2N7") (pinfunction "MIPI_DCPHY_VREG_2N7") (pintype "open_emitter"))
    )
    (net (code "63") (name "Net-(D26-EN)") (class "Default")
      (node (ref "D26") (pin "9") (pinfunction "EN_9") (pintype "passive"))
      (node (ref "R106") (pin "2") (pinfunction "2_2") (pintype "passive"))
      (node (ref "R107") (pin "2") (pinfunction "2_2") (pintype "passive"))
      (node (ref "R109") (pin "2") (pinfunction "2_2") (pintype "passive"))
    )
    (net (code "64") (name "Net-(D26-FB)") (class "Default")
      (node (ref "D26") (pin "2") (pinfunction "FB_2") (pintype "passive"))
      (node (ref "R108") (pin "1") (pinfunction "1_1") (pintype "passive"))
      (node (ref "R110") (pin "1") (pinfunction "1_1") (pintype "passive"))
      (node (ref "R113") (pin "2") (pinfunction "2_2") (pintype "passive"))
    )
    (net (code "65") (name "Net-(D26-IN)") (class "Default")
      (node (ref "C413") (pin "1") (pinfunction "1_1") (pintype "passive"))
      (node (ref "C414") (pin "1") (pinfunction "1_1") (pintype "passive"))
      (node (ref "D26") (pin "7") (pinfunction "IN_7") (pintype "passive"))
      (node (ref "L22") (pin "1") (pinfunction "1_1") (pintype "passive"))
      (node (ref "L23") (pin "2") (pinfunction "2_2") (pintype "passive"))
      (node (ref "R106") (pin "1") (pinfunction "1_1") (pintype "passive"))
    )
    (net (code "66") (name "Net-(D26-LX1)") (class "Default")
      (node (ref "D26") (pin "4") (pinfunction "LX1_4") (pintype "passive"))
      (node (ref "D26") (pin "5") (pinfunction "LX2_5") (pintype "passive"))
      (node (ref "L22") (pin "2") (pinfunction "2_2") (pintype "passive"))
      (node (ref "VD43") (pin "2") (pinfunction "A_2") (pintype "passive"))
    )
    (net (code "67") (name "Net-(D27-ILM)") (class "Default")
      (node (ref "D27") (pin "3") (pinfunction "ILM_3") (pintype "passive"))
      (node (ref "R244") (pin "2") (pinfunction "2_2") (pintype "passive"))
    )
    (net (code "68") (name "Net-(D48-AUX)") (class "Default")
      (node (ref "D48") (pin "8") (pinfunction "AUX_8") (pintype "passive"))
      (node (ref "R494") (pin "1") (pinfunction "1_1") (pintype "passive"))
    )
    (net (code "69") (name "Net-(D48-VBAT)") (class "Default")
      (node (ref "D48") (pin "7") (pinfunction "VBAT_7") (pintype "passive"))
      (node (ref "R493") (pin "2") (pinfunction "2_2") (pintype "passive"))
    )
    (net (code "70") (name "Net-(D48-VREF)") (class "Default")
      (node (ref "D48") (pin "9") (pinfunction "VREF_9") (pintype "passive"))
      (node (ref "R495") (pin "2") (pinfunction "2_2") (pintype "passive"))
    )
    (net (code "71") (name "Net-(R232-Pad2)") (class "Default")
      (node (ref "R232") (pin "2") (pinfunction "2_2") (pintype "passive"))
      (node (ref "R233") (pin "1") (pinfunction "1_1") (pintype "passive"))
      (node (ref "X22") (pin "10") (pinfunction "10_10") (pintype "passive"))
    )
    (net (code "72") (name "Net-(R235-Pad2)") (class "Default")
      (node (ref "R235") (pin "2") (pinfunction "2_2") (pintype "passive"))
      (node (ref "R237") (pin "1") (pinfunction "1_1") (pintype "passive"))
      (node (ref "X22") (pin "11") (pinfunction "11_11") (pintype "passive"))
    )
    (net (code "73") (name "VCC5V0_SYS_S5") (class "Default")
      (node (ref "L23") (pin "1") (pinfunction "1_1") (pintype "passive"))
    )
    (net (code "74") (name "VCCA_1V8_S0") (class "Default")
      (node (ref "C403") (pin "1") (pinfunction "1_1") (pintype "passive"))
      (node (ref "C404") (pin "1") (pinfunction "1_1") (pintype "passive"))
      (node (ref "C407") (pin "1") (pinfunction "1_1") (pintype "passive"))
      (node (ref "D2") (pin "1W20") (pinfunction "MIPI_DPHY_CSI1/2_RX_AVDD1V8_1W20") (pintype "power_in"))
      (node (ref "D2") (pin "2D12") (pinfunction "MIPI_DPHY_CSI3/4_RX_AVDD1V8_2D12") (pintype "power_in"))
      (node (ref "D2") (pin "2P8") (pinfunction "MIPI_DCPHY_AVDD1V8_2P8") (pintype "open_emitter"))
    )
    (net (code "75") (name "VCC_3V3_S0") (class "Default")
      (node (ref "C408") (pin "2") (pinfunction "2_2") (pintype "passive"))
      (node (ref "C409") (pin "2") (pinfunction "2_2") (pintype "passive"))
      (node (ref "X23") (pin "22") (pinfunction "22_22") (pintype "passive"))
    )
    (net (code "76") (name "VCC_3V3_S3") (class "Default")
      (node (ref "C415") (pin "1") (pinfunction "1_1") (pintype "passive"))
      (node (ref "C416") (pin "1") (pinfunction "1_1") (pintype "passive"))
      (node (ref "D27") (pin "5") (pinfunction "VIN_5") (pintype "passive"))
    )
    (net (code "77") (name "VCC_LEDA2") (class "Default")
      (node (ref "C412") (pin "2") (pinfunction "2_2") (pintype "passive"))
      (node (ref "D26") (pin "8") (pinfunction "OVP_8") (pintype "passive"))
      (node (ref "VD43") (pin "1") (pinfunction "K_1") (pintype "passive"))
      (node (ref "X22") (pin "4") (pinfunction "4_4") (pintype "passive"))
      (node (ref "X22") (pin "5") (pinfunction "5_5") (pintype "passive"))
    )
    (net (code "78") (name "VCC_LEDK2") (class "Default")
      (node (ref "R108") (pin "2") (pinfunction "2_2") (pintype "passive"))
      (node (ref "R110") (pin "2") (pinfunction "2_2") (pintype "passive"))
      (node (ref "R111") (pin "1") (pinfunction "1_1") (pintype "passive"))
      (node (ref "R112") (pin "1") (pinfunction "1_1") (pintype "passive"))
      (node (ref "X22") (pin "1") (pinfunction "1_1") (pintype "passive"))
      (node (ref "X22") (pin "2") (pinfunction "2_2") (pintype "passive"))
    )
    (net (code "79") (name "VDDA_0V75_S0") (class "Default")
      (node (ref "C401") (pin "1") (pinfunction "1_1") (pintype "passive"))
      (node (ref "C405") (pin "2") (pinfunction "2_2") (pintype "passive"))
      (node (ref "C406") (pin "1") (pinfunction "1_1") (pintype "passive"))
      (node (ref "C410") (pin "2") (pinfunction "2_2") (pintype "passive"))
      (node (ref "C411") (pin "1") (pinfunction "1_1") (pintype "passive"))
      (node (ref "D2") (pin "2D11") (pinfunction "MIPI_DPHY_CSI3/4_RX_AVDD0V75_2D11") (pintype "power_in"))
      (node (ref "D2") (pin "2L11") (pinfunction "MIPI_DPHY_CSI1/2_RX_AVDD0V75_2L11") (pintype "power_in"))
      (node (ref "D2") (pin "2M7") (pinfunction "MIPI_DCPHY_AVDD_2M7") (pintype "open_emitter"))
    )
    (net (code "80") (name "VDDA_1V2_S0") (class "Default")
      (node (ref "C402") (pin "1") (pinfunction "1_1") (pintype "passive"))
      (node (ref "D2") (pin "2M8") (pinfunction "MIPI_DCPHY_AVDD1V2_2M8") (pintype "open_emitter"))
    )
    (net (code "81") (name "unconnected-(D2D-MIPI_DPHY_CSI2_RX_CLKN-Pad1AD22)") (class "Default")
      (node (ref "D2") (pin "1AD22") (pinfunction "MIPI_DPHY_CSI2_RX_CLKN_1AD22") (pintype "input+no_connect"))
    )
    (net (code "82") (name "unconnected-(D2D-MIPI_DPHY_CSI2_RX_CLKP-Pad1AD21)") (class "Default")
      (node (ref "D2") (pin "1AD21") (pinfunction "MIPI_DPHY_CSI2_RX_CLKP_1AD21") (pintype "input+no_connect"))
    )
    (net (code "83") (name "unconnected-(D2D-MIPI_DPHY_CSI3_RX_CLKN-Pad1H23)") (class "Default")
      (node (ref "D2") (pin "1H23") (pinfunction "MIPI_DPHY_CSI3_RX_CLKN_1H23") (pintype "input+no_connect"))
    )
    (net (code "84") (name "unconnected-(D2D-MIPI_DPHY_CSI3_RX_CLKP-Pad1H22)") (class "Default")
      (node (ref "D2") (pin "1H22") (pinfunction "MIPI_DPHY_CSI3_RX_CLKP_1H22") (pintype "input+no_connect"))
    )
    (net (code "85") (name "unconnected-(D2D-MIPI_DPHY_CSI3_RX_D0N-PadH29)") (class "Default")
      (node (ref "D2") (pin "H29") (pinfunction "MIPI_DPHY_CSI3_RX_D0N_H29") (pintype "input+no_connect"))
    )
    (net (code "86") (name "unconnected-(D2D-MIPI_DPHY_CSI3_RX_D0P-PadH28)") (class "Default")
      (node (ref "D2") (pin "H28") (pinfunction "MIPI_DPHY_CSI3_RX_D0P_H28") (pintype "input+no_connect"))
    )
    (net (code "87") (name "unconnected-(D2D-MIPI_DPHY_CSI3_RX_D1N-PadJ29)") (class "Default")
      (node (ref "D2") (pin "J29") (pinfunction "MIPI_DPHY_CSI3_RX_D1N_J29") (pintype "input+no_connect"))
    )
    (net (code "88") (name "unconnected-(D2D-MIPI_DPHY_CSI3_RX_D1P-PadJ28)") (class "Default")
      (node (ref "D2") (pin "J28") (pinfunction "MIPI_DPHY_CSI3_RX_D1P_J28") (pintype "input+no_connect"))
    )
    (net (code "89") (name "unconnected-(D2D-MIPI_DPHY_CSI3_RX_D2N-PadK29)") (class "Default")
      (node (ref "D2") (pin "K29") (pinfunction "MIPI_DPHY_CSI3_RX_D2N_K29") (pintype "input+no_connect"))
    )
    (net (code "90") (name "unconnected-(D2D-MIPI_DPHY_CSI3_RX_D2P-PadK28)") (class "Default")
      (node (ref "D2") (pin "K28") (pinfunction "MIPI_DPHY_CSI3_RX_D2P_K28") (pintype "input+no_connect"))
    )
    (net (code "91") (name "unconnected-(D2D-MIPI_DPHY_CSI3_RX_D3N-PadL29)") (class "Default")
      (node (ref "D2") (pin "L29") (pinfunction "MIPI_DPHY_CSI3_RX_D3N_L29") (pintype "input+no_connect"))
    )
    (net (code "92") (name "unconnected-(D2D-MIPI_DPHY_CSI3_RX_D3P-PadL28)") (class "Default")
      (node (ref "D2") (pin "L28") (pinfunction "MIPI_DPHY_CSI3_RX_D3P_L28") (pintype "input+no_connect"))
    )
    (net (code "93") (name "unconnected-(D2D-MIPI_DPHY_CSI4_RX_CLKN-Pad1K23)") (class "Default")
      (node (ref "D2") (pin "1K23") (pinfunction "MIPI_DPHY_CSI4_RX_CLKN_1K23") (pintype "input+no_connect"))
    )
    (net (code "94") (name "unconnected-(D2D-MIPI_DPHY_CSI4_RX_CLKP-Pad1K22)") (class "Default")
      (node (ref "D2") (pin "1K22") (pinfunction "MIPI_DPHY_CSI4_RX_CLKP_1K22") (pintype "input+no_connect"))
    )
    (net (code "95") (name "unconnected-(D26-NC-Pad1)") (class "Default")
      (node (ref "D26") (pin "1") (pinfunction "NC_1") (pintype "passive+no_connect"))
    )
    (net (code "96") (name "unconnected-(D26-NC-Pad3)") (class "Default")
      (node (ref "D26") (pin "3") (pinfunction "NC_3") (pintype "passive+no_connect"))
    )
    (net (code "97") (name "unconnected-(D26-NC3-Pad6)") (class "Default")
      (node (ref "D26") (pin "6") (pinfunction "NC3_6") (pintype "passive+no_connect"))
    )
    (net (code "98") (name "unconnected-(D26-NC4-Pad10)") (class "Default")
      (node (ref "D26") (pin "10") (pinfunction "NC4_10") (pintype "passive+no_connect"))
    )
    (net (code "99") (name "unconnected-(D48-BUSY-Pad13)") (class "Default")
      (node (ref "D48") (pin "13") (pinfunction "BUSY_13") (pintype "passive+no_connect"))
    )
    (net (code "100") (name "unconnected-(X22-Pad3)") (class "Default")
      (node (ref "X22") (pin "3") (pinfunction "3_3") (pintype "passive+no_connect"))
    )
    (net (code "101") (name "unconnected-(X22-Pad6)") (class "Default")
      (node (ref "X22") (pin "6") (pinfunction "6_6") (pintype "passive+no_connect"))
    )
    (net (code "102") (name "unconnected-(X22-Pad7)") (class "Default")
      (node (ref "X22") (pin "7") (pinfunction "7_7") (pintype "passive+no_connect"))
    )
    (net (code "103") (name "unconnected-(X22-Pad8)") (class "Default")
      (node (ref "X22") (pin "8") (pinfunction "8_8") (pintype "passive+no_connect"))
    )
  )
)
